# real_time_clock.net
KiCad netlist of a schematic drawn in Altium Designer
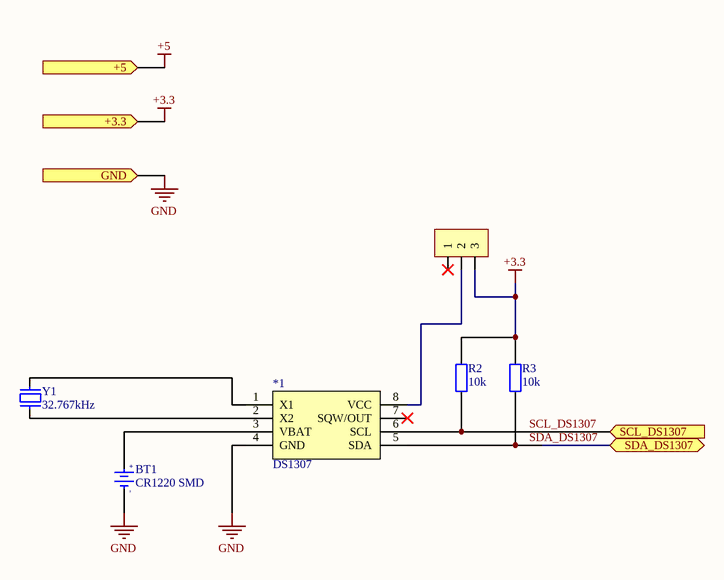
[diagram p0: real_time_clock.SchDoc]

(export (version "E")
  (design (tool "Eeschema 10.0.6"))
  (components
    (comp (ref "*1") (value "DS1307") (footprint "SOIC 8") (libsource (lib "TrungVan_Lib") (part "DS1307")))
    (comp (ref "BT1")
      (value "CR1220 SMD")
      (footprint "DE PIN CR1220")
      (libsource (lib "TrungVan_Lib") (part "De pin CR1220 SMD"))
    )
    (comp (ref "JP1")
      (value "JP 1x3 2.54")
      (footprint "JP 1x3 DT")
      (description "Cắm")
      (libsource (lib "TrungVan_Lib") (part "JP 1x3 2.54 Duc Thang"))
    )
    (comp (ref "R2")
      (value "10k")
      (footprint "tro smd 0805")
      (description "Dán")
      (libsource (lib "TrungVan_Lib") (part "Tro 0805 1% 10k"))
    )
    (comp (ref "R3")
      (value "10k")
      (footprint "tro smd 0805")
      (description "Dán")
      (libsource (lib "TrungVan_Lib") (part "Tro 0805 1% 10k"))
    )
    (comp (ref "Y1")
      (value "32.767kHz")
      (footprint "Thach Anh 2 Chan 32,768 KHz")
      (description "Crystal For all Crystal 2pin.")
      (libsource (lib "TrungVan_Lib") (part "Thach Anh 2 chan 32,768 Khz"))
    )
  )
  (nets
    (net (code "1") (name "+3.3") (class "Default")
      (node (ref "JP1") (pin "3") (pinfunction "3_3") (pintype "passive"))
      (node (ref "R2") (pin "2") (pinfunction "2_2") (pintype "passive"))
      (node (ref "R3") (pin "2") (pinfunction "2_2") (pintype "passive"))
    )
    (net (code "3") (name "/SCL_DS1307") (class "Default")
      (node (ref "*1") (pin "6") (pinfunction "SCL_6") (pintype "passive"))
      (node (ref "R2") (pin "1") (pinfunction "1_1") (pintype "passive"))
    )
    (net (code "4") (name "/SDA_DS1307") (class "Default")
      (node (ref "*1") (pin "5") (pinfunction "SDA_5") (pintype "passive"))
      (node (ref "R3") (pin "1") (pinfunction "1_1") (pintype "passive"))
    )
    (net (code "5") (name "GND") (class "Default")
      (node (ref "*1") (pin "4") (pinfunction "GND_4") (pintype "passive"))
      (node (ref "BT1") (pin "2") (pinfunction "GND_2") (pintype "passive"))
    )
    (net (code "6") (name "Net-(*1-VBAT)") (class "Default")
      (node (ref "*1") (pin "3") (pinfunction "VBAT_3") (pintype "passive"))
      (node (ref "BT1") (pin "1") (pinfunction "+3V_1") (pintype "passive"))
    )
    (net (code "7") (name "Net-(*1-VCC)") (class "Default")
      (node (ref "*1") (pin "8") (pinfunction "VCC_8") (pintype "passive"))
      (node (ref "JP1") (pin "2") (pinfunction "2_2") (pintype "passive"))
    )
    (net (code "8") (name "Net-(*1-X1)") (class "Default")
      (node (ref "*1") (pin "1") (pinfunction "X1_1") (pintype "passive"))
      (node (ref "Y1") (pin "2") (pinfunction "2_2") (pintype "passive"))
    )
    (net (code "9") (name "Net-(*1-X2)") (class "Default")
      (node (ref "*1") (pin "2") (pinfunction "X2_2") (pintype "passive"))
      (node (ref "Y1") (pin "1") (pinfunction "1_1") (pintype "passive"))
    )
    (net (code "10") (name "unconnected-(*1-SQW{slash}OUT-Pad7)") (class "Default")
      (node (ref "*1") (pin "7") (pinfunction "SQW/OUT_7") (pintype "passive+no_connect"))
    )
    (net (code "11") (name "unconnected-(JP1-Pad1)") (class "Default")
      (node (ref "JP1") (pin "1") (pinfunction "1_1") (pintype "passive+no_connect"))
    )
  )
)
